# main-stm32-pdipopto.net
KiCad netlist of a schematic drawn in EAGLE
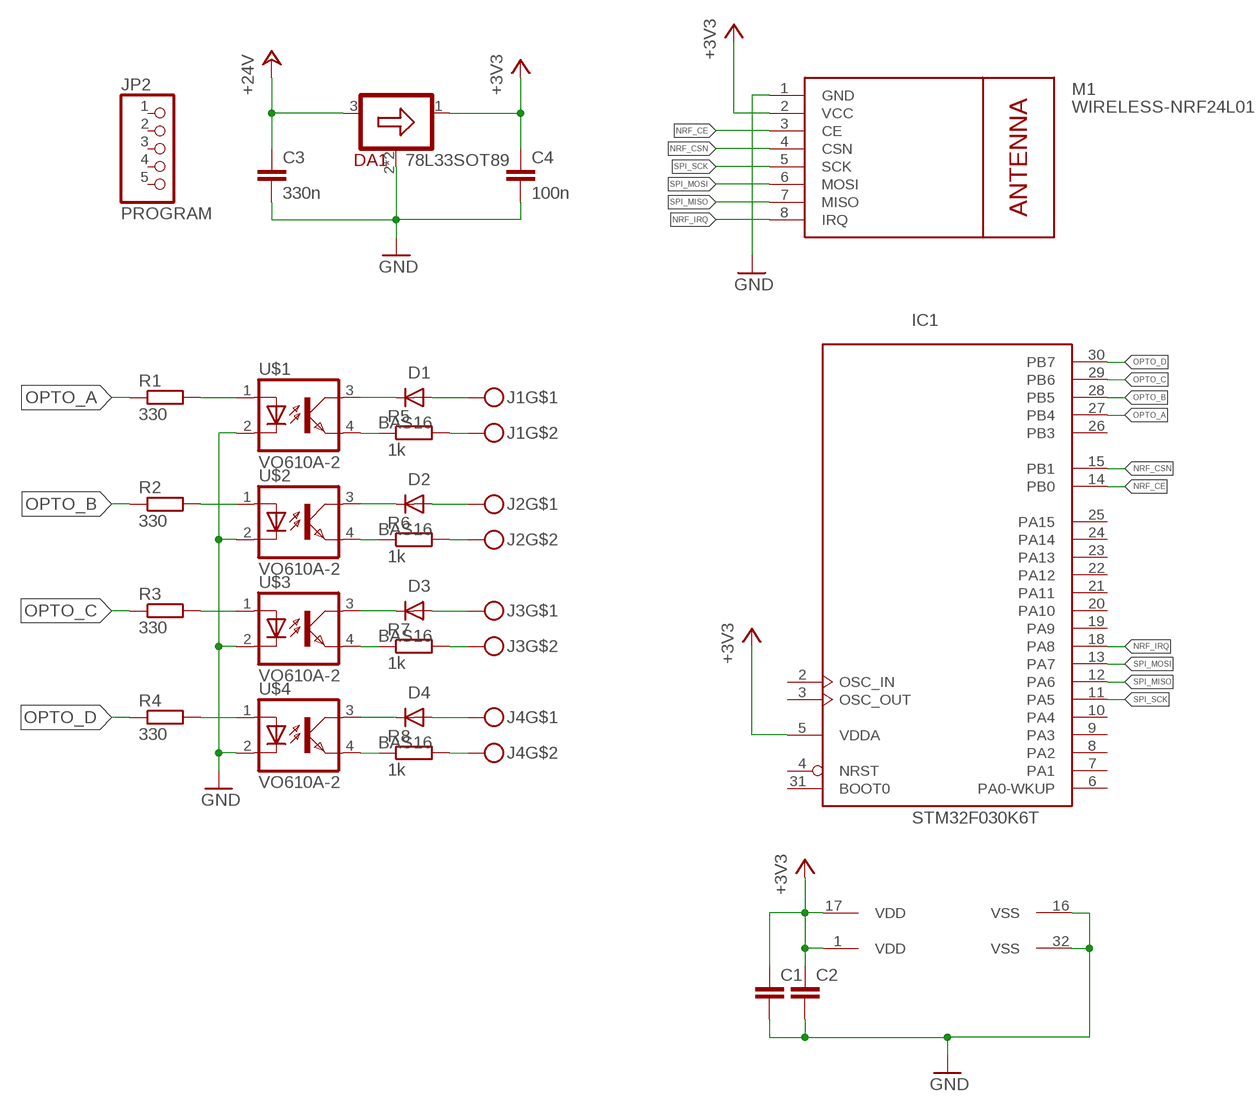
[diagram p0: schematic, sheet 1]

(export (version "E")
  (design (tool "Eeschema 10.0.6"))
  (components
    (comp (ref "C1")
      (value "C-EUC1206")
      (footprint "eagle-import:C1206")
      (libsource (lib "eagle-import") (part "C-EUC1206"))
    )
    (comp (ref "C2")
      (value "C-EUC1206")
      (footprint "eagle-import:C1206")
      (libsource (lib "eagle-import") (part "C-EUC1206"))
    )
    (comp (ref "C3")
      (value "330n")
      (footprint "eagle-import:C1206")
      (libsource (lib "eagle-import") (part "C-EUC1206"))
    )
    (comp (ref "C4")
      (value "100n")
      (footprint "eagle-import:C1206")
      (libsource (lib "eagle-import") (part "C-EUC1206"))
    )
    (comp (ref "D1")
      (value "BAS16")
      (footprint "eagle-import:SOT23")
      (libsource (lib "eagle-import") (part "BAS16"))
    )
    (comp (ref "D2")
      (value "BAS16")
      (footprint "eagle-import:SOT23")
      (libsource (lib "eagle-import") (part "BAS16"))
    )
    (comp (ref "D3")
      (value "BAS16")
      (footprint "eagle-import:SOT23")
      (libsource (lib "eagle-import") (part "BAS16"))
    )
    (comp (ref "D4")
      (value "BAS16")
      (footprint "eagle-import:SOT23")
      (libsource (lib "eagle-import") (part "BAS16"))
    )
    (comp (ref "DA1")
      (value "78L33SOT89")
      (footprint "eagle-import:SOT89")
      (libsource (lib "eagle-import") (part "78L33SOT89"))
    )
    (comp (ref "IC1")
      (value "STM32F030K6T")
      (footprint "eagle-import:LQFP32")
      (libsource (lib "eagle-import") (part "STM32F030KT6"))
    )
    (comp (ref "J1")
      (value "SCREW-TERMINAL-2PIN")
      (footprint "eagle-import:PITCH4.3-PIN2")
      (libsource (lib "eagle-import") (part "SCREW-TERMINAL-2PIN"))
    )
    (comp (ref "J2")
      (value "SCREW-TERMINAL-2PIN")
      (footprint "eagle-import:PITCH4.3-PIN2")
      (libsource (lib "eagle-import") (part "SCREW-TERMINAL-2PIN"))
    )
    (comp (ref "J3")
      (value "SCREW-TERMINAL-2PIN")
      (footprint "eagle-import:PITCH4.3-PIN2")
      (libsource (lib "eagle-import") (part "SCREW-TERMINAL-2PIN"))
    )
    (comp (ref "J4")
      (value "SCREW-TERMINAL-2PIN")
      (footprint "eagle-import:PITCH4.3-PIN2")
      (libsource (lib "eagle-import") (part "SCREW-TERMINAL-2PIN"))
    )
    (comp (ref "JP2")
      (value "PROGRAM")
      (footprint "eagle-import:1X05")
      (libsource (lib "eagle-import") (part "PINHD-1X5"))
    )
    (comp (ref "M1")
      (value "WIRELESS-NRF24L01")
      (footprint "eagle-import:WIRELESS-NRF24L01")
      (libsource (lib "eagle-import") (part "WIRELESS-NRF24L01"))
    )
    (comp (ref "R1")
      (value "330")
      (footprint "eagle-import:R1206")
      (libsource (lib "eagle-import") (part "R-EU_R1206"))
    )
    (comp (ref "R2")
      (value "330")
      (footprint "eagle-import:R1206")
      (libsource (lib "eagle-import") (part "R-EU_R1206"))
    )
    (comp (ref "R3")
      (value "330")
      (footprint "eagle-import:R1206")
      (libsource (lib "eagle-import") (part "R-EU_R1206"))
    )
    (comp (ref "R4")
      (value "330")
      (footprint "eagle-import:R1206")
      (libsource (lib "eagle-import") (part "R-EU_R1206"))
    )
    (comp (ref "R5")
      (value "1k")
      (footprint "eagle-import:R1206")
      (libsource (lib "eagle-import") (part "R-EU_R1206"))
    )
    (comp (ref "R6")
      (value "1k")
      (footprint "eagle-import:R1206")
      (libsource (lib "eagle-import") (part "R-EU_R1206"))
    )
    (comp (ref "R7")
      (value "1k")
      (footprint "eagle-import:R1206")
      (libsource (lib "eagle-import") (part "R-EU_R1206"))
    )
    (comp (ref "R8")
      (value "1k")
      (footprint "eagle-import:R1206")
      (libsource (lib "eagle-import") (part "R-EU_R1206"))
    )
    (comp (ref "U$1")
      (value "VO610A-2")
      (footprint "eagle-import:DIL04")
      (libsource (lib "eagle-import") (part "VO610A-2"))
    )
    (comp (ref "U$2")
      (value "VO610A-2")
      (footprint "eagle-import:DIL04")
      (libsource (lib "eagle-import") (part "VO610A-2"))
    )
    (comp (ref "U$3")
      (value "VO610A-2")
      (footprint "eagle-import:DIL04")
      (libsource (lib "eagle-import") (part "VO610A-2"))
    )
    (comp (ref "U$4")
      (value "VO610A-2")
      (footprint "eagle-import:DIL04")
      (libsource (lib "eagle-import") (part "VO610A-2"))
    )
  )
  (nets
    (net (code "1") (name "+3V3") (class "Default")
      (node (ref "C1") (pin "1") (pinfunction "1_1") (pintype "passive"))
      (node (ref "C2") (pin "1") (pinfunction "1_1") (pintype "passive"))
      (node (ref "C4") (pin "1") (pinfunction "1_1") (pintype "passive"))
      (node (ref "DA1") (pin "1") (pinfunction "OUT_1") (pintype "power_in"))
      (node (ref "IC1") (pin "1") (pinfunction "VDD_1") (pintype "power_in"))
      (node (ref "IC1") (pin "17") (pinfunction "VDD_17") (pintype "power_in"))
      (node (ref "IC1") (pin "5") (pinfunction "VDDA_5") (pintype "power_in"))
      (node (ref "M1") (pin "2") (pinfunction "VCC_2") (pintype "power_in"))
    )
    (net (code "2") (name "+24V") (class "Default")
      (node (ref "C3") (pin "1") (pinfunction "1_1") (pintype "passive"))
      (node (ref "DA1") (pin "3") (pinfunction "IN_3") (pintype "power_in"))
    )
    (net (code "3") (name "GND") (class "Default")
      (node (ref "C1") (pin "2") (pinfunction "2_2") (pintype "passive"))
      (node (ref "C2") (pin "2") (pinfunction "2_2") (pintype "passive"))
      (node (ref "C3") (pin "2") (pinfunction "2_2") (pintype "passive"))
      (node (ref "C4") (pin "2") (pinfunction "2_2") (pintype "passive"))
      (node (ref "DA1") (pin "2") (pinfunction "GND_2") (pintype "power_in"))
      (node (ref "DA1") (pin "2@1") (pinfunction "GND_2@1") (pintype "power_in"))
      (node (ref "IC1") (pin "16") (pinfunction "VSS_16") (pintype "power_in"))
      (node (ref "IC1") (pin "32") (pinfunction "VSS_32") (pintype "power_in"))
      (node (ref "M1") (pin "1") (pinfunction "GND_1") (pintype "power_in"))
      (node (ref "U$1") (pin "2") (pinfunction "C_2") (pintype "passive"))
      (node (ref "U$2") (pin "2") (pinfunction "C_2") (pintype "passive"))
      (node (ref "U$3") (pin "2") (pinfunction "C_2") (pintype "passive"))
      (node (ref "U$4") (pin "2") (pinfunction "C_2") (pintype "passive"))
    )
    (net (code "4") (name "NRF_CE") (class "Default")
      (node (ref "IC1") (pin "14") (pinfunction "PB0_14") (pintype "bidirectional"))
      (node (ref "M1") (pin "3") (pinfunction "CE_3") (pintype "bidirectional"))
    )
    (net (code "5") (name "NRF_CSN") (class "Default")
      (node (ref "IC1") (pin "15") (pinfunction "PB1_15") (pintype "bidirectional"))
      (node (ref "M1") (pin "4") (pinfunction "CSN_4") (pintype "bidirectional"))
    )
    (net (code "6") (name "NRF_IRQ") (class "Default")
      (node (ref "IC1") (pin "18") (pinfunction "PA8_18") (pintype "bidirectional"))
      (node (ref "M1") (pin "8") (pinfunction "IRQ_8") (pintype "bidirectional"))
    )
    (net (code "7") (name "Net-(D1-A)") (class "Default")
      (node (ref "D1") (pin "1") (pinfunction "A_1") (pintype "passive"))
      (node (ref "J1") (pin "1") (pinfunction "KL_1") (pintype "passive"))
    )
    (net (code "8") (name "Net-(D1-K)") (class "Default")
      (node (ref "D1") (pin "3") (pinfunction "K_3") (pintype "passive"))
      (node (ref "U$1") (pin "3") (pinfunction "COL_3") (pintype "passive"))
    )
    (net (code "9") (name "Net-(D2-A)") (class "Default")
      (node (ref "D2") (pin "1") (pinfunction "A_1") (pintype "passive"))
      (node (ref "J2") (pin "1") (pinfunction "KL_1") (pintype "passive"))
    )
    (net (code "10") (name "Net-(D2-K)") (class "Default")
      (node (ref "D2") (pin "3") (pinfunction "K_3") (pintype "passive"))
      (node (ref "U$2") (pin "3") (pinfunction "COL_3") (pintype "passive"))
    )
    (net (code "11") (name "Net-(D3-A)") (class "Default")
      (node (ref "D3") (pin "1") (pinfunction "A_1") (pintype "passive"))
      (node (ref "J3") (pin "1") (pinfunction "KL_1") (pintype "passive"))
    )
    (net (code "12") (name "Net-(D3-K)") (class "Default")
      (node (ref "D3") (pin "3") (pinfunction "K_3") (pintype "passive"))
      (node (ref "U$3") (pin "3") (pinfunction "COL_3") (pintype "passive"))
    )
    (net (code "13") (name "Net-(D4-A)") (class "Default")
      (node (ref "D4") (pin "1") (pinfunction "A_1") (pintype "passive"))
      (node (ref "J4") (pin "1") (pinfunction "KL_1") (pintype "passive"))
    )
    (net (code "14") (name "Net-(D4-K)") (class "Default")
      (node (ref "D4") (pin "3") (pinfunction "K_3") (pintype "passive"))
      (node (ref "U$4") (pin "3") (pinfunction "COL_3") (pintype "passive"))
    )
    (net (code "15") (name "Net-(J1B-KL)") (class "Default")
      (node (ref "J1") (pin "2") (pinfunction "KL_2") (pintype "passive"))
      (node (ref "R5") (pin "2") (pinfunction "2_2") (pintype "passive"))
    )
    (net (code "16") (name "Net-(J2B-KL)") (class "Default")
      (node (ref "J2") (pin "2") (pinfunction "KL_2") (pintype "passive"))
      (node (ref "R6") (pin "2") (pinfunction "2_2") (pintype "passive"))
    )
    (net (code "17") (name "Net-(J3B-KL)") (class "Default")
      (node (ref "J3") (pin "2") (pinfunction "KL_2") (pintype "passive"))
      (node (ref "R7") (pin "2") (pinfunction "2_2") (pintype "passive"))
    )
    (net (code "18") (name "Net-(J4B-KL)") (class "Default")
      (node (ref "J4") (pin "2") (pinfunction "KL_2") (pintype "passive"))
      (node (ref "R8") (pin "2") (pinfunction "2_2") (pintype "passive"))
    )
    (net (code "19") (name "Net-(U$1-A)") (class "Default")
      (node (ref "R1") (pin "2") (pinfunction "2_2") (pintype "passive"))
      (node (ref "U$1") (pin "1") (pinfunction "A_1") (pintype "passive"))
    )
    (net (code "20") (name "Net-(U$1-EMIT)") (class "Default")
      (node (ref "R5") (pin "1") (pinfunction "1_1") (pintype "passive"))
      (node (ref "U$1") (pin "4") (pinfunction "EMIT_4") (pintype "passive"))
    )
    (net (code "21") (name "Net-(U$2-A)") (class "Default")
      (node (ref "R2") (pin "2") (pinfunction "2_2") (pintype "passive"))
      (node (ref "U$2") (pin "1") (pinfunction "A_1") (pintype "passive"))
    )
    (net (code "22") (name "Net-(U$2-EMIT)") (class "Default")
      (node (ref "R6") (pin "1") (pinfunction "1_1") (pintype "passive"))
      (node (ref "U$2") (pin "4") (pinfunction "EMIT_4") (pintype "passive"))
    )
    (net (code "23") (name "Net-(U$3-A)") (class "Default")
      (node (ref "R3") (pin "2") (pinfunction "2_2") (pintype "passive"))
      (node (ref "U$3") (pin "1") (pinfunction "A_1") (pintype "passive"))
    )
    (net (code "24") (name "Net-(U$3-EMIT)") (class "Default")
      (node (ref "R7") (pin "1") (pinfunction "1_1") (pintype "passive"))
      (node (ref "U$3") (pin "4") (pinfunction "EMIT_4") (pintype "passive"))
    )
    (net (code "25") (name "Net-(U$4-A)") (class "Default")
      (node (ref "R4") (pin "2") (pinfunction "2_2") (pintype "passive"))
      (node (ref "U$4") (pin "1") (pinfunction "A_1") (pintype "passive"))
    )
    (net (code "26") (name "Net-(U$4-EMIT)") (class "Default")
      (node (ref "R8") (pin "1") (pinfunction "1_1") (pintype "passive"))
      (node (ref "U$4") (pin "4") (pinfunction "EMIT_4") (pintype "passive"))
    )
    (net (code "27") (name "OPTO_A") (class "Default")
      (node (ref "IC1") (pin "27") (pinfunction "PB4_27") (pintype "bidirectional"))
      (node (ref "R1") (pin "1") (pinfunction "1_1") (pintype "passive"))
    )
    (net (code "28") (name "OPTO_B") (class "Default")
      (node (ref "IC1") (pin "28") (pinfunction "PB5_28") (pintype "bidirectional"))
      (node (ref "R2") (pin "1") (pinfunction "1_1") (pintype "passive"))
    )
    (net (code "29") (name "OPTO_C") (class "Default")
      (node (ref "IC1") (pin "29") (pinfunction "PB6_29") (pintype "bidirectional"))
      (node (ref "R3") (pin "1") (pinfunction "1_1") (pintype "passive"))
    )
    (net (code "30") (name "OPTO_D") (class "Default")
      (node (ref "IC1") (pin "30") (pinfunction "PB7_30") (pintype "bidirectional"))
      (node (ref "R4") (pin "1") (pinfunction "1_1") (pintype "passive"))
    )
    (net (code "31") (name "SPI_MISO") (class "Default")
      (node (ref "IC1") (pin "12") (pinfunction "PA6_12") (pintype "bidirectional"))
      (node (ref "M1") (pin "7") (pinfunction "MISO_7") (pintype "bidirectional"))
    )
    (net (code "32") (name "SPI_MOSI") (class "Default")
      (node (ref "IC1") (pin "13") (pinfunction "PA7_13") (pintype "bidirectional"))
      (node (ref "M1") (pin "6") (pinfunction "MOSI_6") (pintype "bidirectional"))
    )
    (net (code "33") (name "SPI_SCK") (class "Default")
      (node (ref "IC1") (pin "11") (pinfunction "PA5_11") (pintype "bidirectional"))
      (node (ref "M1") (pin "5") (pinfunction "SCK_5") (pintype "bidirectional"))
    )
    (net (code "34") (name "unconnected-(IC1A-BOOT0-Pad31)") (class "Default")
      (node (ref "IC1") (pin "31") (pinfunction "BOOT0_31") (pintype "input"))
    )
    (net (code "35") (name "unconnected-(IC1A-NRST-Pad4)") (class "Default")
      (node (ref "IC1") (pin "4") (pinfunction "NRST_4") (pintype "bidirectional"))
    )
    (net (code "36") (name "unconnected-(IC1A-OSC_IN-Pad2)") (class "Default")
      (node (ref "IC1") (pin "2") (pinfunction "OSC_IN_2") (pintype "bidirectional"))
    )
    (net (code "37") (name "unconnected-(IC1A-OSC_OUT-Pad3)") (class "Default")
      (node (ref "IC1") (pin "3") (pinfunction "OSC_OUT_3") (pintype "bidirectional"))
    )
    (net (code "38") (name "unconnected-(IC1A-PA0-WKUP-Pad6)") (class "Default")
      (node (ref "IC1") (pin "6") (pinfunction "PA0-WKUP_6") (pintype "bidirectional"))
    )
    (net (code "39") (name "unconnected-(IC1A-PA1-Pad7)") (class "Default")
      (node (ref "IC1") (pin "7") (pinfunction "PA1_7") (pintype "bidirectional"))
    )
    (net (code "40") (name "unconnected-(IC1A-PA2-Pad8)") (class "Default")
      (node (ref "IC1") (pin "8") (pinfunction "PA2_8") (pintype "bidirectional"))
    )
    (net (code "41") (name "unconnected-(IC1A-PA3-Pad9)") (class "Default")
      (node (ref "IC1") (pin "9") (pinfunction "PA3_9") (pintype "bidirectional"))
    )
    (net (code "42") (name "unconnected-(IC1A-PA4-Pad10)") (class "Default")
      (node (ref "IC1") (pin "10") (pinfunction "PA4_10") (pintype "bidirectional"))
    )
    (net (code "43") (name "unconnected-(IC1A-PA9-Pad19)") (class "Default")
      (node (ref "IC1") (pin "19") (pinfunction "PA9_19") (pintype "bidirectional"))
    )
    (net (code "44") (name "unconnected-(IC1A-PA10-Pad20)") (class "Default")
      (node (ref "IC1") (pin "20") (pinfunction "PA10_20") (pintype "bidirectional"))
    )
    (net (code "45") (name "unconnected-(IC1A-PA11-Pad21)") (class "Default")
      (node (ref "IC1") (pin "21") (pinfunction "PA11_21") (pintype "bidirectional"))
    )
    (net (code "46") (name "unconnected-(IC1A-PA12-Pad22)") (class "Default")
      (node (ref "IC1") (pin "22") (pinfunction "PA12_22") (pintype "bidirectional"))
    )
    (net (code "47") (name "unconnected-(IC1A-PA13-Pad23)") (class "Default")
      (node (ref "IC1") (pin "23") (pinfunction "PA13_23") (pintype "bidirectional"))
    )
    (net (code "48") (name "unconnected-(IC1A-PA14-Pad24)") (class "Default")
      (node (ref "IC1") (pin "24") (pinfunction "PA14_24") (pintype "bidirectional"))
    )
    (net (code "49") (name "unconnected-(IC1A-PA15-Pad25)") (class "Default")
      (node (ref "IC1") (pin "25") (pinfunction "PA15_25") (pintype "bidirectional"))
    )
    (net (code "50") (name "unconnected-(IC1A-PB3-Pad26)") (class "Default")
      (node (ref "IC1") (pin "26") (pinfunction "PB3_26") (pintype "bidirectional"))
    )
    (net (code "51") (name "unconnected-(JP2-Pad1)") (class "Default")
      (node (ref "JP2") (pin "1") (pinfunction "1_1") (pintype "passive"))
    )
    (net (code "52") (name "unconnected-(JP2-Pad2)") (class "Default")
      (node (ref "JP2") (pin "2") (pinfunction "2_2") (pintype "passive"))
    )
    (net (code "53") (name "unconnected-(JP2-Pad3)") (class "Default")
      (node (ref "JP2") (pin "3") (pinfunction "3_3") (pintype "passive"))
    )
    (net (code "54") (name "unconnected-(JP2-Pad4)") (class "Default")
      (node (ref "JP2") (pin "4") (pinfunction "4_4") (pintype "passive"))
    )
    (net (code "55") (name "unconnected-(JP2-Pad5)") (class "Default")
      (node (ref "JP2") (pin "5") (pinfunction "5_5") (pintype "passive"))
    )
  )
)
